# music_box.net
KiCad netlist of a schematic drawn in EAGLE
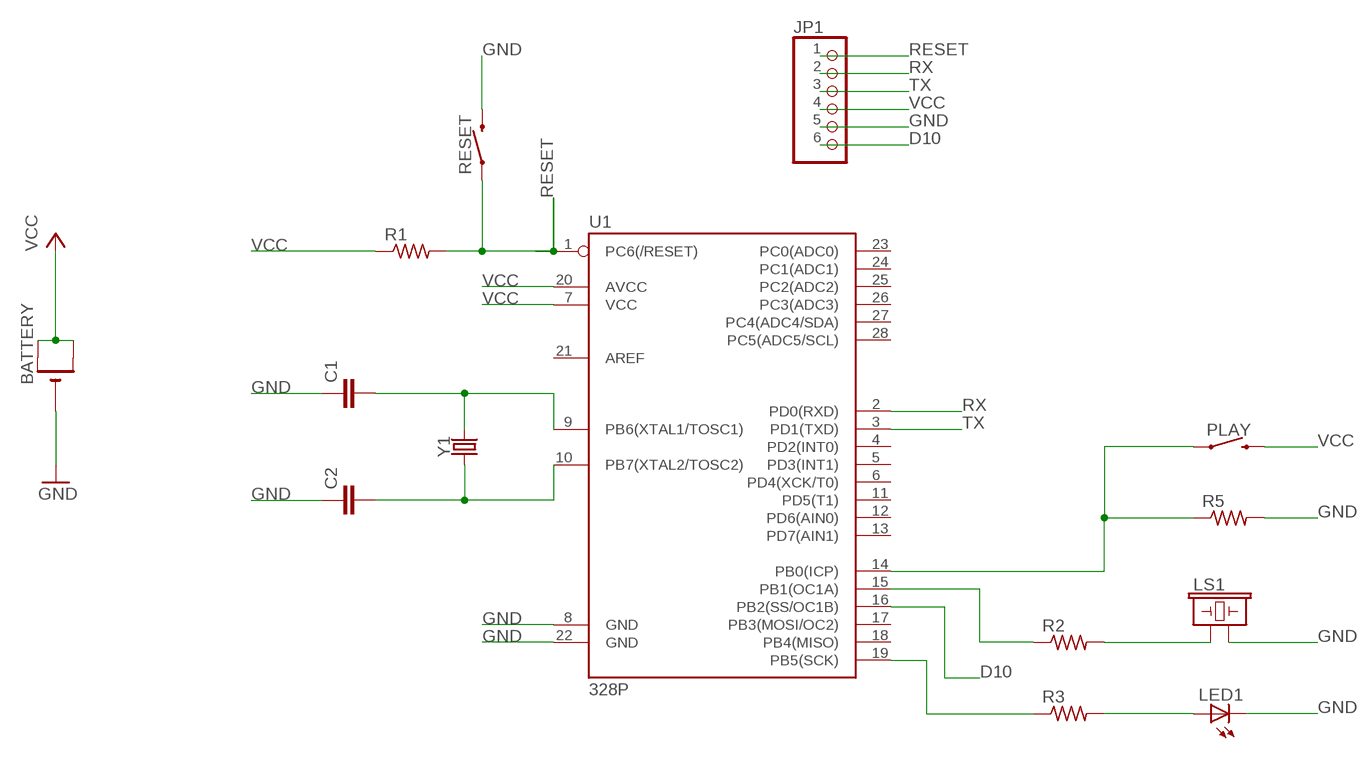
[diagram p0: schematic, sheet 1]

(export (version "E")
  (design (tool "Eeschema 10.0.6"))
  (components
    (comp (ref "BATTERY")
      (value "CR1220THM")
      (footprint "eagle-import:CR1220-THM")
      (libsource (lib "eagle-import") (part "CR1220THM"))
    )
    (comp (ref "C1")
      (value "22PF-PTH-2.54MM-200V-5%")
      (footprint "eagle-import:CAP-PTH-2.54")
      (libsource (lib "eagle-import") (part "22PF-PTH-2.54MM-200V-5%"))
    )
    (comp (ref "C2")
      (value "22PF-PTH-2.54MM-200V-5%")
      (footprint "eagle-import:CAP-PTH-2.54")
      (libsource (lib "eagle-import") (part "22PF-PTH-2.54MM-200V-5%"))
    )
    (comp (ref "JP1")
      (value "PINHD-1X6B")
      (footprint "eagle-import:1X06-BIG")
      (libsource (lib "eagle-import") (part "PINHD-1X6B"))
    )
    (comp (ref "LED1")
      (value "LED5MM")
      (footprint "eagle-import:LED5MM")
      (libsource (lib "eagle-import") (part "LED5MM"))
    )
    (comp (ref "LS1")
      (value "BUZZER-PTH")
      (footprint "eagle-import:BUZZER-12MM")
      (libsource (lib "eagle-import") (part "BUZZER-PTH"))
    )
    (comp (ref "PLAY")
      (value "MOMENTARY-SWITCH-SPST-PTH-6.0MM")
      (footprint "eagle-import:TACTILE_SWITCH_PTH_6.0MM")
      (libsource (lib "eagle-import") (part "MOMENTARY-SWITCH-SPST-PTH-6.0MM"))
    )
    (comp (ref "R1")
      (value "R-US_0207/7")
      (footprint "eagle-import:0207_7")
      (libsource (lib "eagle-import") (part "R-US_0207/7"))
    )
    (comp (ref "R2")
      (value "R-US_0207/7")
      (footprint "eagle-import:0207_7")
      (libsource (lib "eagle-import") (part "R-US_0207/7"))
    )
    (comp (ref "R3")
      (value "R-US_0207/7")
      (footprint "eagle-import:0207_7")
      (libsource (lib "eagle-import") (part "R-US_0207/7"))
    )
    (comp (ref "R5")
      (value "R-US_0207/7")
      (footprint "eagle-import:0207_7")
      (libsource (lib "eagle-import") (part "R-US_0207/7"))
    )
    (comp (ref "RESET")
      (value "MOMENTARY-SWITCH-SPST-PTH-6.0MM")
      (footprint "eagle-import:TACTILE_SWITCH_PTH_6.0MM")
      (libsource (lib "eagle-import") (part "MOMENTARY-SWITCH-SPST-PTH-6.0MM"))
    )
    (comp (ref "U1")
      (value "328P")
      (footprint "eagle-import:DIP28")
      (libsource (lib "eagle-import") (part "ATMEGA328P_PDIP"))
    )
    (comp (ref "Y1")
      (value "CRYSTAL-16MHZPTH-HC49US")
      (footprint "eagle-import:HC49US")
      (libsource (lib "eagle-import") (part "CRYSTAL-16MHZPTH-HC49US"))
    )
  )
  (nets
    (net (code "1") (name "/D10") (class "Default")
      (node (ref "JP1") (pin "6") (pinfunction "6_6") (pintype "passive"))
      (node (ref "U1") (pin "16") (pinfunction "PB2(SS/OC1B)_16") (pintype "bidirectional"))
    )
    (net (code "2") (name "/RESET") (class "Default")
      (node (ref "JP1") (pin "1") (pinfunction "1_1") (pintype "passive"))
      (node (ref "R1") (pin "2") (pinfunction "2_2") (pintype "passive"))
      (node (ref "RESET") (pin "1") (pinfunction "1_1") (pintype "passive"))
      (node (ref "U1") (pin "1") (pinfunction "PC6(/RESET)_1") (pintype "bidirectional"))
    )
    (net (code "3") (name "/RX") (class "Default")
      (node (ref "JP1") (pin "2") (pinfunction "2_2") (pintype "passive"))
      (node (ref "U1") (pin "2") (pinfunction "PD0(RXD)_2") (pintype "bidirectional"))
    )
    (net (code "4") (name "/TX") (class "Default")
      (node (ref "JP1") (pin "3") (pinfunction "3_3") (pintype "passive"))
      (node (ref "U1") (pin "3") (pinfunction "PD1(TXD)_3") (pintype "bidirectional"))
    )
    (net (code "5") (name "GND") (class "Default")
      (node (ref "BATTERY") (pin "-") (pinfunction "-_-") (pintype "passive"))
      (node (ref "C1") (pin "1") (pinfunction "1_1") (pintype "passive"))
      (node (ref "C2") (pin "1") (pinfunction "1_1") (pintype "passive"))
      (node (ref "JP1") (pin "5") (pinfunction "5_5") (pintype "passive"))
      (node (ref "LED1") (pin "K") (pinfunction "C_K") (pintype "passive"))
      (node (ref "LS1") (pin "-") (pinfunction "2_-") (pintype "passive"))
      (node (ref "R5") (pin "2") (pinfunction "2_2") (pintype "passive"))
      (node (ref "RESET") (pin "3") (pinfunction "2_3") (pintype "passive"))
      (node (ref "U1") (pin "22") (pinfunction "GND_22") (pintype "bidirectional"))
      (node (ref "U1") (pin "8") (pinfunction "GND_8") (pintype "bidirectional"))
    )
    (net (code "6") (name "Net-(LED1-PadA)") (class "Default")
      (node (ref "LED1") (pin "A") (pinfunction "A_A") (pintype "passive"))
      (node (ref "R3") (pin "2") (pinfunction "2_2") (pintype "passive"))
    )
    (net (code "7") (name "Net-(LS1-1)") (class "Default")
      (node (ref "LS1") (pin "+") (pinfunction "1_+") (pintype "passive"))
      (node (ref "R2") (pin "2") (pinfunction "2_2") (pintype "passive"))
    )
    (net (code "8") (name "Net-(U1-PB0(ICP))") (class "Default")
      (node (ref "PLAY") (pin "1") (pinfunction "1_1") (pintype "passive"))
      (node (ref "R5") (pin "1") (pinfunction "1_1") (pintype "passive"))
      (node (ref "U1") (pin "14") (pinfunction "PB0(ICP)_14") (pintype "bidirectional"))
    )
    (net (code "9") (name "Net-(U1-PB1(OC1A))") (class "Default")
      (node (ref "R2") (pin "1") (pinfunction "1_1") (pintype "passive"))
      (node (ref "U1") (pin "15") (pinfunction "PB1(OC1A)_15") (pintype "bidirectional"))
    )
    (net (code "10") (name "Net-(U1-PB5(SCK))") (class "Default")
      (node (ref "R3") (pin "1") (pinfunction "1_1") (pintype "passive"))
      (node (ref "U1") (pin "19") (pinfunction "PB5(SCK)_19") (pintype "bidirectional"))
    )
    (net (code "11") (name "Net-(U1-PB6(XTAL1{slash}TOSC1))") (class "Default")
      (node (ref "C1") (pin "2") (pinfunction "2_2") (pintype "passive"))
      (node (ref "U1") (pin "9") (pinfunction "PB6(XTAL1/TOSC1)_9") (pintype "bidirectional"))
      (node (ref "Y1") (pin "2") (pinfunction "2_2") (pintype "passive"))
    )
    (net (code "12") (name "Net-(U1-PB7(XTAL2{slash}TOSC2))") (class "Default")
      (node (ref "C2") (pin "2") (pinfunction "2_2") (pintype "passive"))
      (node (ref "U1") (pin "10") (pinfunction "PB7(XTAL2/TOSC2)_10") (pintype "bidirectional"))
      (node (ref "Y1") (pin "1") (pinfunction "1_1") (pintype "passive"))
    )
    (net (code "13") (name "VCC") (class "Default")
      (node (ref "BATTERY") (pin "+1") (pinfunction "+_+1") (pintype "passive"))
      (node (ref "BATTERY") (pin "+2") (pinfunction "+1_+2") (pintype "passive"))
      (node (ref "JP1") (pin "4") (pinfunction "4_4") (pintype "passive"))
      (node (ref "PLAY") (pin "3") (pinfunction "2_3") (pintype "passive"))
      (node (ref "R1") (pin "1") (pinfunction "1_1") (pintype "passive"))
      (node (ref "U1") (pin "20") (pinfunction "AVCC_20") (pintype "bidirectional"))
      (node (ref "U1") (pin "7") (pinfunction "VCC_7") (pintype "bidirectional"))
    )
    (net (code "14") (name "unconnected-(U1-AREF-Pad21)") (class "Default")
      (node (ref "U1") (pin "21") (pinfunction "AREF_21") (pintype "bidirectional"))
    )
    (net (code "15") (name "unconnected-(U1-PB3(MOSI{slash}OC2)-Pad17)") (class "Default")
      (node (ref "U1") (pin "17") (pinfunction "PB3(MOSI/OC2)_17") (pintype "bidirectional"))
    )
    (net (code "16") (name "unconnected-(U1-PB4(MISO)-Pad18)") (class "Default")
      (node (ref "U1") (pin "18") (pinfunction "PB4(MISO)_18") (pintype "bidirectional"))
    )
    (net (code "17") (name "unconnected-(U1-PC0(ADC0)-Pad23)") (class "Default")
      (node (ref "U1") (pin "23") (pinfunction "PC0(ADC0)_23") (pintype "bidirectional"))
    )
    (net (code "18") (name "unconnected-(U1-PC1(ADC1)-Pad24)") (class "Default")
      (node (ref "U1") (pin "24") (pinfunction "PC1(ADC1)_24") (pintype "bidirectional"))
    )
    (net (code "19") (name "unconnected-(U1-PC2(ADC2)-Pad25)") (class "Default")
      (node (ref "U1") (pin "25") (pinfunction "PC2(ADC2)_25") (pintype "bidirectional"))
    )
    (net (code "20") (name "unconnected-(U1-PC3(ADC3)-Pad26)") (class "Default")
      (node (ref "U1") (pin "26") (pinfunction "PC3(ADC3)_26") (pintype "bidirectional"))
    )
    (net (code "21") (name "unconnected-(U1-PC4(ADC4{slash}SDA)-Pad27)") (class "Default")
      (node (ref "U1") (pin "27") (pinfunction "PC4(ADC4/SDA)_27") (pintype "bidirectional"))
    )
    (net (code "22") (name "unconnected-(U1-PC5(ADC5{slash}SCL)-Pad28)") (class "Default")
      (node (ref "U1") (pin "28") (pinfunction "PC5(ADC5/SCL)_28") (pintype "bidirectional"))
    )
    (net (code "23") (name "unconnected-(U1-PD2(INT0)-Pad4)") (class "Default")
      (node (ref "U1") (pin "4") (pinfunction "PD2(INT0)_4") (pintype "bidirectional"))
    )
    (net (code "24") (name "unconnected-(U1-PD3(INT1)-Pad5)") (class "Default")
      (node (ref "U1") (pin "5") (pinfunction "PD3(INT1)_5") (pintype "bidirectional"))
    )
    (net (code "25") (name "unconnected-(U1-PD4(XCK{slash}T0)-Pad6)") (class "Default")
      (node (ref "U1") (pin "6") (pinfunction "PD4(XCK/T0)_6") (pintype "bidirectional"))
    )
    (net (code "26") (name "unconnected-(U1-PD5(T1)-Pad11)") (class "Default")
      (node (ref "U1") (pin "11") (pinfunction "PD5(T1)_11") (pintype "bidirectional"))
    )
    (net (code "27") (name "unconnected-(U1-PD6(AIN0)-Pad12)") (class "Default")
      (node (ref "U1") (pin "12") (pinfunction "PD6(AIN0)_12") (pintype "bidirectional"))
    )
    (net (code "28") (name "unconnected-(U1-PD7(AIN1)-Pad13)") (class "Default")
      (node (ref "U1") (pin "13") (pinfunction "PD7(AIN1)_13") (pintype "bidirectional"))
    )
  )
)
